# 6_CAN_schdoc.net
KiCad netlist of a schematic drawn in Altium Designer
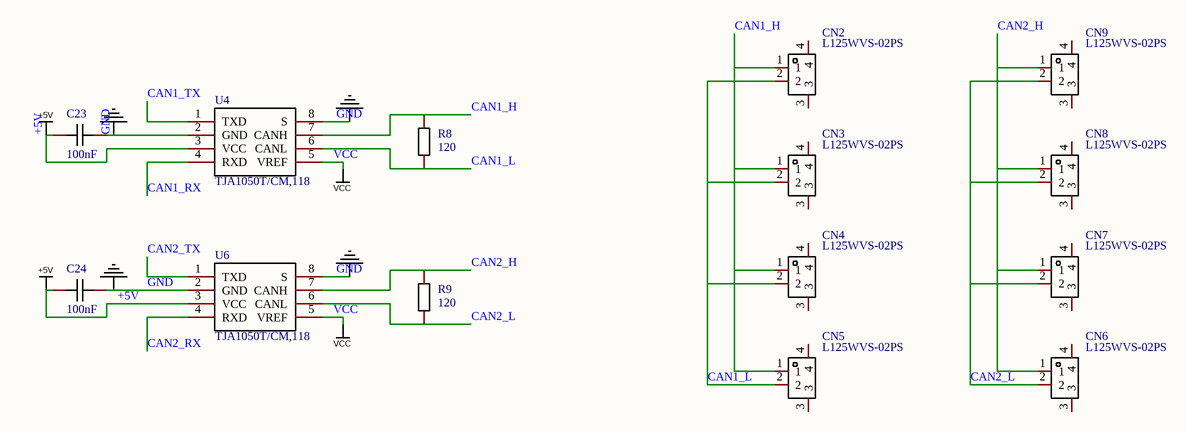
[diagram p0: 6_CAN.schdoc.schdoc]

(export (version "E")
  (design (tool "Eeschema 10.0.6"))
  (components
    (comp (ref "C23")
      (value "100nF")
      (fields (field (name "NAME") "100nF"))
      (libsource (lib "altium-import") (part "root_0_CAP_0603_"))
    )
    (comp (ref "C24")
      (value "100nF")
      (fields (field (name "NAME") "100nF"))
      (libsource (lib "altium-import") (part "root_0_CAP_0603_"))
    )
    (comp (ref "CN2")
      (value "L125WVS-02PS")
      (description "插针结构:1x2P;间距:1.25mm;公母:公;安装方式:立贴;排数:1;每排PIN数:2;额定电流:1A;工作温度范围:-40℃~+110℃;")
      (fields (field (name "NAME") "L125WVS-02PS") (field (name "MANUFACTURER") "DEALON(德艺隆)"))
      (libsource (lib "altium-import") (part "root_0_L125WVS-02PS_"))
    )
    (comp (ref "CN3")
      (value "L125WVS-02PS")
      (description "插针结构:1x2P;间距:1.25mm;公母:公;安装方式:立贴;排数:1;每排PIN数:2;额定电流:1A;工作温度范围:-40℃~+110℃;")
      (fields (field (name "NAME") "L125WVS-02PS") (field (name "MANUFACTURER") "DEALON(德艺隆)"))
      (libsource (lib "altium-import") (part "root_0_L125WVS-02PS_"))
    )
    (comp (ref "CN4")
      (value "L125WVS-02PS")
      (description "插针结构:1x2P;间距:1.25mm;公母:公;安装方式:立贴;排数:1;每排PIN数:2;额定电流:1A;工作温度范围:-40℃~+110℃;")
      (fields (field (name "NAME") "L125WVS-02PS") (field (name "MANUFACTURER") "DEALON(德艺隆)"))
      (libsource (lib "altium-import") (part "root_0_L125WVS-02PS_"))
    )
    (comp (ref "CN5")
      (value "L125WVS-02PS")
      (description "插针结构:1x2P;间距:1.25mm;公母:公;安装方式:立贴;排数:1;每排PIN数:2;额定电流:1A;工作温度范围:-40℃~+110℃;")
      (fields (field (name "NAME") "L125WVS-02PS") (field (name "MANUFACTURER") "DEALON(德艺隆)"))
      (libsource (lib "altium-import") (part "root_0_L125WVS-02PS_"))
    )
    (comp (ref "CN6")
      (value "L125WVS-02PS")
      (description "插针结构:1x2P;间距:1.25mm;公母:公;安装方式:立贴;排数:1;每排PIN数:2;额定电流:1A;工作温度范围:-40℃~+110℃;")
      (fields (field (name "NAME") "L125WVS-02PS") (field (name "MANUFACTURER") "DEALON(德艺隆)"))
      (libsource (lib "altium-import") (part "root_0_L125WVS-02PS_"))
    )
    (comp (ref "CN7")
      (value "L125WVS-02PS")
      (description "插针结构:1x2P;间距:1.25mm;公母:公;安装方式:立贴;排数:1;每排PIN数:2;额定电流:1A;工作温度范围:-40℃~+110℃;")
      (fields (field (name "NAME") "L125WVS-02PS") (field (name "MANUFACTURER") "DEALON(德艺隆)"))
      (libsource (lib "altium-import") (part "root_0_L125WVS-02PS_"))
    )
    (comp (ref "CN8")
      (value "L125WVS-02PS")
      (description "插针结构:1x2P;间距:1.25mm;公母:公;安装方式:立贴;排数:1;每排PIN数:2;额定电流:1A;工作温度范围:-40℃~+110℃;")
      (fields (field (name "NAME") "L125WVS-02PS") (field (name "MANUFACTURER") "DEALON(德艺隆)"))
      (libsource (lib "altium-import") (part "root_0_L125WVS-02PS_"))
    )
    (comp (ref "CN9")
      (value "L125WVS-02PS")
      (description "插针结构:1x2P;间距:1.25mm;公母:公;安装方式:立贴;排数:1;每排PIN数:2;额定电流:1A;工作温度范围:-40℃~+110℃;")
      (fields (field (name "NAME") "L125WVS-02PS") (field (name "MANUFACTURER") "DEALON(德艺隆)"))
      (libsource (lib "altium-import") (part "root_0_L125WVS-02PS_"))
    )
    (comp (ref "R8")
      (value "120")
      (fields (field (name "NAME") "120"))
      (libsource (lib "altium-import") (part "root_3_mirrored_Res_0603_"))
    )
    (comp (ref "R9")
      (value "120")
      (fields (field (name "NAME") "120"))
      (libsource (lib "altium-import") (part "root_3_mirrored_Res_0603_"))
    )
    (comp (ref "U4")
      (value "TJA1050T/CM,118")
      (description "类型:收发器;")
      (fields (field (name "NAME") "TJA1050T/CM,118") (field (name "MANUFACTURER") "NXP(恩智浦)"))
      (libsource (lib "altium-import") (part "root_0_TJA1050T/CM,118_"))
    )
    (comp (ref "U6")
      (value "TJA1050T/CM,118")
      (description "类型:收发器;")
      (fields (field (name "NAME") "TJA1050T/CM,118") (field (name "MANUFACTURER") "NXP(恩智浦)"))
      (libsource (lib "altium-import") (part "root_0_TJA1050T/CM,118_"))
    )
  )
  (nets
    (net (code "1") (name "+5V") (class "Default")
      (node (ref "C23") (pin "1") (pinfunction "1_1") (pintype "passive"))
      (node (ref "C24") (pin "1") (pinfunction "1_1") (pintype "passive"))
      (node (ref "U4") (pin "3") (pinfunction "VCC_3") (pintype "passive"))
      (node (ref "U6") (pin "3") (pinfunction "VCC_3") (pintype "passive"))
    )
    (net (code "2") (name "/CAN1_H") (class "Default")
      (node (ref "CN2") (pin "1") (pinfunction "1_1") (pintype "passive"))
      (node (ref "CN3") (pin "1") (pinfunction "1_1") (pintype "passive"))
      (node (ref "CN4") (pin "1") (pinfunction "1_1") (pintype "passive"))
      (node (ref "CN5") (pin "1") (pinfunction "1_1") (pintype "passive"))
      (node (ref "R8") (pin "1") (pinfunction "1_1") (pintype "passive"))
      (node (ref "U4") (pin "7") (pinfunction "CANH_7") (pintype "passive"))
    )
    (net (code "3") (name "/CAN1_L") (class "Default")
      (node (ref "CN2") (pin "2") (pinfunction "2_2") (pintype "passive"))
      (node (ref "CN3") (pin "2") (pinfunction "2_2") (pintype "passive"))
      (node (ref "CN4") (pin "2") (pinfunction "2_2") (pintype "passive"))
      (node (ref "CN5") (pin "2") (pinfunction "2_2") (pintype "passive"))
      (node (ref "R8") (pin "2") (pinfunction "2_2") (pintype "passive"))
      (node (ref "U4") (pin "6") (pinfunction "CANL_6") (pintype "passive"))
    )
    (net (code "4") (name "/CAN1_RX") (class "Default")
      (node (ref "U4") (pin "4") (pinfunction "RXD_4") (pintype "passive"))
    )
    (net (code "5") (name "/CAN1_TX") (class "Default")
      (node (ref "U4") (pin "1") (pinfunction "TXD_1") (pintype "passive"))
    )
    (net (code "6") (name "/CAN2_H") (class "Default")
      (node (ref "CN6") (pin "1") (pinfunction "1_1") (pintype "passive"))
      (node (ref "CN7") (pin "1") (pinfunction "1_1") (pintype "passive"))
      (node (ref "CN8") (pin "1") (pinfunction "1_1") (pintype "passive"))
      (node (ref "CN9") (pin "1") (pinfunction "1_1") (pintype "passive"))
      (node (ref "R9") (pin "1") (pinfunction "1_1") (pintype "passive"))
      (node (ref "U6") (pin "7") (pinfunction "CANH_7") (pintype "passive"))
    )
    (net (code "7") (name "/CAN2_L") (class "Default")
      (node (ref "CN6") (pin "2") (pinfunction "2_2") (pintype "passive"))
      (node (ref "CN7") (pin "2") (pinfunction "2_2") (pintype "passive"))
      (node (ref "CN8") (pin "2") (pinfunction "2_2") (pintype "passive"))
      (node (ref "CN9") (pin "2") (pinfunction "2_2") (pintype "passive"))
      (node (ref "R9") (pin "2") (pinfunction "2_2") (pintype "passive"))
      (node (ref "U6") (pin "6") (pinfunction "CANL_6") (pintype "passive"))
    )
    (net (code "8") (name "/CAN2_RX") (class "Default")
      (node (ref "U6") (pin "4") (pinfunction "RXD_4") (pintype "passive"))
    )
    (net (code "9") (name "/CAN2_TX") (class "Default")
      (node (ref "U6") (pin "1") (pinfunction "TXD_1") (pintype "passive"))
    )
    (net (code "10") (name "/GND") (class "Default")
      (node (ref "C23") (pin "2") (pinfunction "2_2") (pintype "passive"))
      (node (ref "C24") (pin "2") (pinfunction "2_2") (pintype "passive"))
      (node (ref "U4") (pin "2") (pinfunction "GND_2") (pintype "passive"))
      (node (ref "U4") (pin "8") (pinfunction "S_8") (pintype "passive"))
      (node (ref "U6") (pin "2") (pinfunction "GND_2") (pintype "passive"))
      (node (ref "U6") (pin "8") (pinfunction "S_8") (pintype "passive"))
    )
    (net (code "11") (name "VCC") (class "Default")
      (node (ref "U4") (pin "5") (pinfunction "VREF_5") (pintype "passive"))
      (node (ref "U6") (pin "5") (pinfunction "VREF_5") (pintype "passive"))
    )
    (net (code "12") (name "unconnected-(CN2-Pad3)") (class "Default")
      (node (ref "CN2") (pin "3") (pinfunction "3_3") (pintype "passive"))
    )
    (net (code "13") (name "unconnected-(CN2-Pad4)") (class "Default")
      (node (ref "CN2") (pin "4") (pinfunction "4_4") (pintype "passive"))
    )
    (net (code "14") (name "unconnected-(CN3-Pad3)") (class "Default")
      (node (ref "CN3") (pin "3") (pinfunction "3_3") (pintype "passive"))
    )
    (net (code "15") (name "unconnected-(CN3-Pad4)") (class "Default")
      (node (ref "CN3") (pin "4") (pinfunction "4_4") (pintype "passive"))
    )
    (net (code "16") (name "unconnected-(CN4-Pad3)") (class "Default")
      (node (ref "CN4") (pin "3") (pinfunction "3_3") (pintype "passive"))
    )
    (net (code "17") (name "unconnected-(CN4-Pad4)") (class "Default")
      (node (ref "CN4") (pin "4") (pinfunction "4_4") (pintype "passive"))
    )
    (net (code "18") (name "unconnected-(CN5-Pad3)") (class "Default")
      (node (ref "CN5") (pin "3") (pinfunction "3_3") (pintype "passive"))
    )
    (net (code "19") (name "unconnected-(CN5-Pad4)") (class "Default")
      (node (ref "CN5") (pin "4") (pinfunction "4_4") (pintype "passive"))
    )
    (net (code "20") (name "unconnected-(CN6-Pad3)") (class "Default")
      (node (ref "CN6") (pin "3") (pinfunction "3_3") (pintype "passive"))
    )
    (net (code "21") (name "unconnected-(CN6-Pad4)") (class "Default")
      (node (ref "CN6") (pin "4") (pinfunction "4_4") (pintype "passive"))
    )
    (net (code "22") (name "unconnected-(CN7-Pad3)") (class "Default")
      (node (ref "CN7") (pin "3") (pinfunction "3_3") (pintype "passive"))
    )
    (net (code "23") (name "unconnected-(CN7-Pad4)") (class "Default")
      (node (ref "CN7") (pin "4") (pinfunction "4_4") (pintype "passive"))
    )
    (net (code "24") (name "unconnected-(CN8-Pad3)") (class "Default")
      (node (ref "CN8") (pin "3") (pinfunction "3_3") (pintype "passive"))
    )
    (net (code "25") (name "unconnected-(CN8-Pad4)") (class "Default")
      (node (ref "CN8") (pin "4") (pinfunction "4_4") (pintype "passive"))
    )
    (net (code "26") (name "unconnected-(CN9-Pad3)") (class "Default")
      (node (ref "CN9") (pin "3") (pinfunction "3_3") (pintype "passive"))
    )
    (net (code "27") (name "unconnected-(CN9-Pad4)") (class "Default")
      (node (ref "CN9") (pin "4") (pinfunction "4_4") (pintype "passive"))
    )
  )
)
